# control_logic.net
KiCad netlist of a schematic drawn in Altium Designer
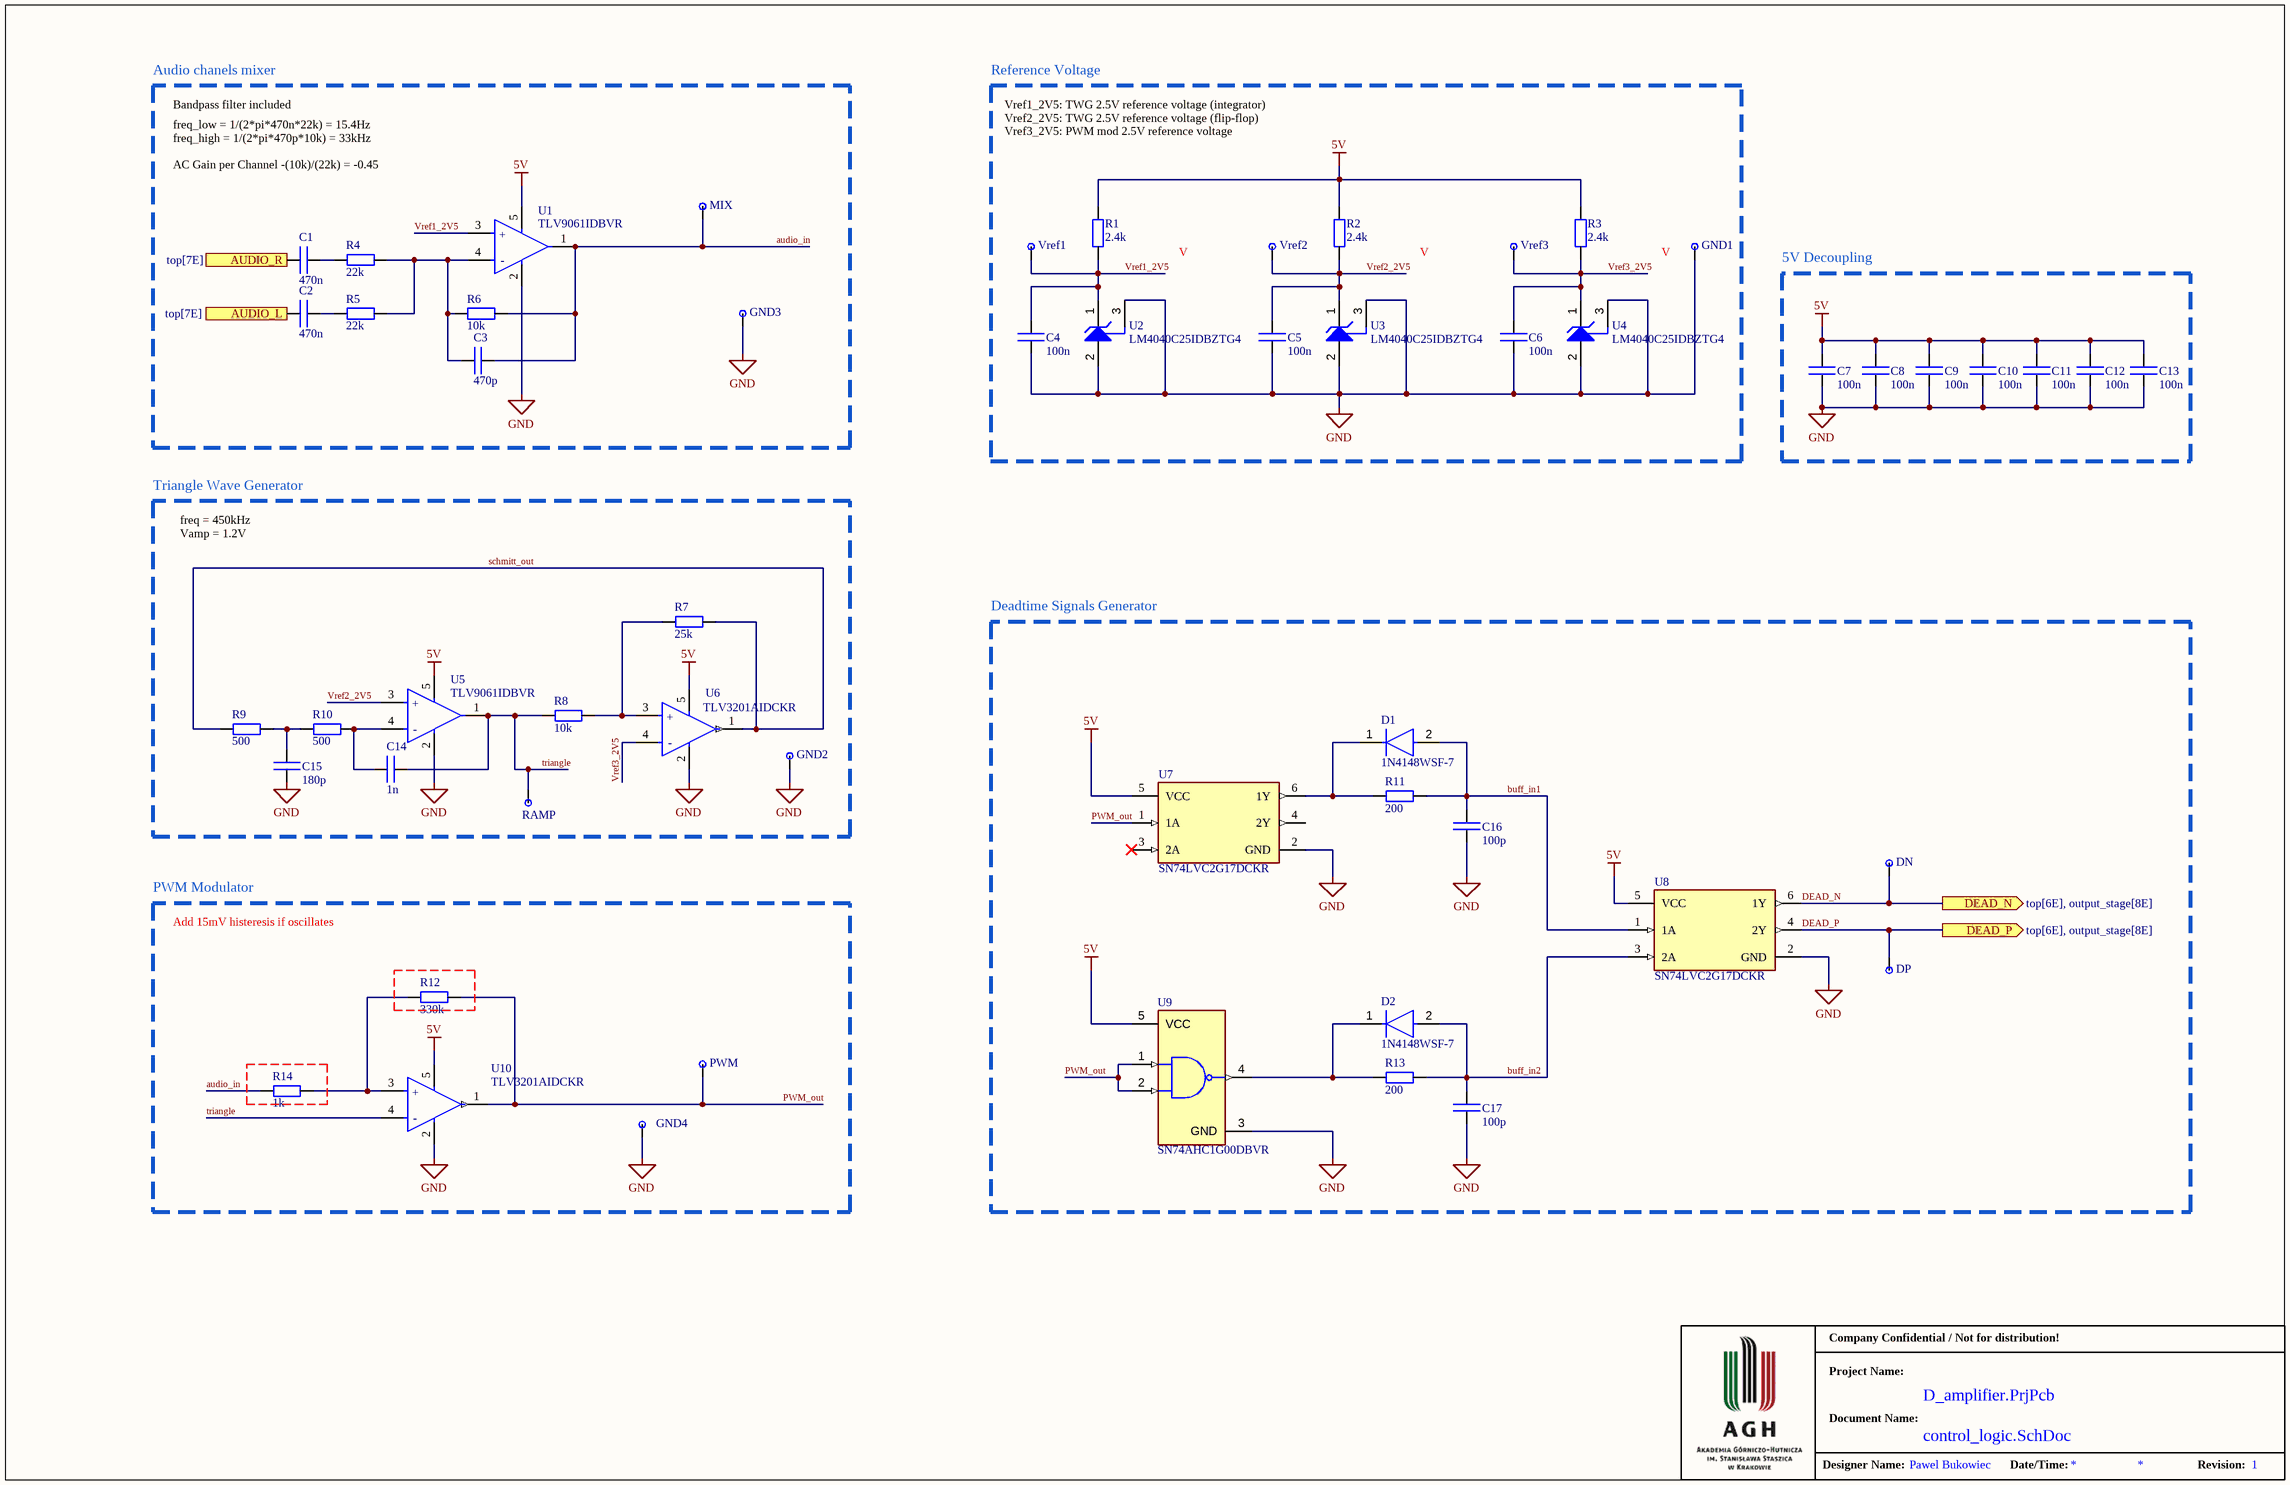
[diagram p0: control_logic.SchDoc]

(export (version "E")
  (design (tool "Eeschema 10.0.6"))
  (components
    (comp (ref "C1") (value "470n") (footprint "CAP_1206") (libsource (lib "INT_lib") (part "Capacitor")))
    (comp (ref "C2") (value "470n") (footprint "CAP_1206") (libsource (lib "INT_lib") (part "Capacitor")))
    (comp (ref "C3")
      (value "470p")
      (footprint "CAP_IPC_0805_133A")
      (fields (field (name "VOLTAGE") "10"))
      (libsource (lib "INT_lib") (part "Capacitor"))
    )
    (comp (ref "C4")
      (value "100n")
      (footprint "CAP_IPC_0805_133A")
      (fields (field (name "VOLTAGE") "16"))
      (libsource (lib "INT_lib") (part "Capacitor"))
    )
    (comp (ref "C5")
      (value "100n")
      (footprint "CAP_IPC_0805_133A")
      (fields (field (name "VOLTAGE") "16"))
      (libsource (lib "INT_lib") (part "Capacitor"))
    )
    (comp (ref "C6")
      (value "100n")
      (footprint "CAP_IPC_0805_133A")
      (fields (field (name "VOLTAGE") "16"))
      (libsource (lib "INT_lib") (part "Capacitor"))
    )
    (comp (ref "C7")
      (value "100n")
      (footprint "CAP_IPC_0805_133A")
      (fields (field (name "VOLTAGE") "16"))
      (libsource (lib "INT_lib") (part "Capacitor"))
    )
    (comp (ref "C8")
      (value "100n")
      (footprint "CAP_IPC_0805_133A")
      (fields (field (name "VOLTAGE") "16"))
      (libsource (lib "INT_lib") (part "Capacitor"))
    )
    (comp (ref "C9")
      (value "100n")
      (footprint "CAP_IPC_0805_133A")
      (fields (field (name "VOLTAGE") "16"))
      (libsource (lib "INT_lib") (part "Capacitor"))
    )
    (comp (ref "C10")
      (value "100n")
      (footprint "CAP_IPC_0805_133A")
      (fields (field (name "VOLTAGE") "16"))
      (libsource (lib "INT_lib") (part "Capacitor"))
    )
    (comp (ref "C11")
      (value "100n")
      (footprint "CAP_IPC_0805_133A")
      (fields (field (name "VOLTAGE") "16"))
      (libsource (lib "INT_lib") (part "Capacitor"))
    )
    (comp (ref "C12")
      (value "100n")
      (footprint "CAP_IPC_0805_133A")
      (fields (field (name "VOLTAGE") "16"))
      (libsource (lib "INT_lib") (part "Capacitor"))
    )
    (comp (ref "C13")
      (value "100n")
      (footprint "CAP_IPC_0805_133A")
      (fields (field (name "VOLTAGE") "16"))
      (libsource (lib "INT_lib") (part "Capacitor"))
    )
    (comp (ref "C14")
      (value "1n")
      (footprint "CAP_IPC_0805_133A")
      (libsource (lib "INT_lib") (part "Capacitor"))
    )
    (comp (ref "C15")
      (value "180p")
      (footprint "CAP_IPC_0805_133A")
      (libsource (lib "INT_lib") (part "Capacitor"))
    )
    (comp (ref "C16")
      (value "100p")
      (footprint "CAP_IPC_0805_133A")
      (libsource (lib "INT_lib") (part "Capacitor"))
    )
    (comp (ref "C17")
      (value "100p")
      (footprint "CAP_IPC_0805_133A")
      (libsource (lib "INT_lib") (part "Capacitor"))
    )
    (comp (ref "D1")
      (value "1N4148WSF-7")
      (footprint "1N4148")
      (description "DIODE GEN PURP 100V 250MA SOD323")
      (fields
        (field (name "MANUFACTURER") "Diodes Inc.")
        (field (name "OCTOPART") "https://octopart.com/1n4148wsf-7-diodes+inc.-33798544")
      )
      (libsource (lib "INT_lib") (part "1N4148"))
    )
    (comp (ref "D2")
      (value "1N4148WSF-7")
      (footprint "1N4148")
      (description "DIODE GEN PURP 100V 250MA SOD323")
      (fields
        (field (name "MANUFACTURER") "Diodes Inc.")
        (field (name "OCTOPART") "https://octopart.com/1n4148wsf-7-diodes+inc.-33798544")
      )
      (libsource (lib "INT_lib") (part "1N4148"))
    )
    (comp (ref "DN")
      (value "TestPoint")
      (footprint "TestPoint_SMT")
      (description "Test Point")
      (libsource (lib "INT_lib") (part "TestPoint"))
    )
    (comp (ref "DP")
      (value "TestPoint")
      (footprint "TestPoint_SMT")
      (description "Test Point")
      (libsource (lib "INT_lib") (part "TestPoint"))
    )
    (comp (ref "GND1")
      (value "TestPoint")
      (footprint "TestPoint_SMT")
      (description "Test Point")
      (libsource (lib "INT_lib") (part "TestPoint"))
    )
    (comp (ref "GND2")
      (value "TestPoint")
      (footprint "TestPoint_SMT")
      (description "Test Point")
      (libsource (lib "INT_lib") (part "TestPoint"))
    )
    (comp (ref "GND3")
      (value "TestPoint")
      (footprint "TestPoint_SMT")
      (description "Test Point")
      (libsource (lib "INT_lib") (part "TestPoint"))
    )
    (comp (ref "GND4")
      (value "TestPoint")
      (footprint "TestPoint_SMT")
      (description "Test Point")
      (libsource (lib "INT_lib") (part "TestPoint"))
    )
    (comp (ref "MIX")
      (value "TestPoint")
      (footprint "TestPoint_SMT")
      (description "Test Point")
      (libsource (lib "INT_lib") (part "TestPoint"))
    )
    (comp (ref "PWM")
      (value "TestPoint")
      (footprint "TestPoint_SMT")
      (description "Test Point")
      (libsource (lib "INT_lib") (part "TestPoint"))
    )
    (comp (ref "R1")
      (value "2.4k")
      (footprint "RES_VJ_0402_MD")
      (libsource (lib "INT_lib") (part "Resistor"))
    )
    (comp (ref "R2")
      (value "2.4k")
      (footprint "RES_VJ_0402_MD")
      (libsource (lib "INT_lib") (part "Resistor"))
    )
    (comp (ref "R3")
      (value "2.4k")
      (footprint "RES_VJ_0402_MD")
      (libsource (lib "INT_lib") (part "Resistor"))
    )
    (comp (ref "R4") (value "22k") (footprint "RES_VJ_0402_MD") (libsource (lib "INT_lib") (part "Resistor")))
    (comp (ref "R5") (value "22k") (footprint "RES_VJ_0402_MD") (libsource (lib "INT_lib") (part "Resistor")))
    (comp (ref "R6") (value "10k") (footprint "RES_VJ_0402_MD") (libsource (lib "INT_lib") (part "Resistor")))
    (comp (ref "R7") (value "25k") (footprint "RES_VJ_0402_MD") (libsource (lib "INT_lib") (part "Resistor")))
    (comp (ref "R8") (value "10k") (footprint "RES_VJ_0402_MD") (libsource (lib "INT_lib") (part "Resistor")))
    (comp (ref "R9") (value "500") (footprint "RES_VJ_0402_MD") (libsource (lib "INT_lib") (part "Resistor")))
    (comp (ref "R10")
      (value "500")
      (footprint "RES_VJ_0402_MD")
      (libsource (lib "INT_lib") (part "Resistor"))
    )
    (comp (ref "R11")
      (value "200")
      (footprint "RES_VJ_0402_MD")
      (libsource (lib "INT_lib") (part "Resistor"))
    )
    (comp (ref "R12")
      (value "330k")
      (footprint "RES_VJ_0402_MD")
      (libsource (lib "INT_lib") (part "Resistor"))
    )
    (comp (ref "R13")
      (value "200")
      (footprint "RES_VJ_0402_MD")
      (libsource (lib "INT_lib") (part "Resistor"))
    )
    (comp (ref "R14") (value "1k") (footprint "RES_VJ_0402_MD") (libsource (lib "INT_lib") (part "Resistor")))
    (comp (ref "RAMP")
      (value "TestPoint")
      (footprint "TestPoint_SMT")
      (description "Test Point")
      (libsource (lib "INT_lib") (part "TestPoint"))
    )
    (comp (ref "U1")
      (value "TLV9061IDBVR")
      (footprint "TLV9061")
      (description "IC CMOS 1 CIRCUIT SOT23-5")
      (libsource (lib "INT_lib") (part "TLV9061"))
    )
    (comp (ref "U2")
      (value "LM4040C25IDBZTG4")
      (footprint "LM4040C25")
      (fields (field (name "MANUFACTURER") "Texas Instruments"))
      (libsource (lib "INT_lib") (part "LM4040C25"))
    )
    (comp (ref "U3")
      (value "LM4040C25IDBZTG4")
      (footprint "LM4040C25")
      (fields (field (name "MANUFACTURER") "Texas Instruments"))
      (libsource (lib "INT_lib") (part "LM4040C25"))
    )
    (comp (ref "U4")
      (value "LM4040C25IDBZTG4")
      (footprint "LM4040C25")
      (fields (field (name "MANUFACTURER") "Texas Instruments"))
      (libsource (lib "INT_lib") (part "LM4040C25"))
    )
    (comp (ref "U5")
      (value "TLV9061IDBVR")
      (footprint "TLV9061")
      (description "IC CMOS 1 CIRCUIT SOT23-5")
      (libsource (lib "INT_lib") (part "TLV9061"))
    )
    (comp (ref "U6")
      (value "TLV3201AIDCKR")
      (footprint "TLV3201")
      (description "IC COMPARATOR RRI SGL SC70-5")
      (libsource (lib "INT_lib") (part "TLV3201"))
    )
    (comp (ref "U7")
      (value "SN74LVC2G17DCKR")
      (footprint "SN74LVC2G17DCKR")
      (description "IC BUF NON-INVERT 5.5V SC70-6")
      (libsource (lib "INT_lib") (part "SN74LVC2G17DCKR"))
    )
    (comp (ref "U8")
      (value "SN74LVC2G17DCKR")
      (footprint "SN74LVC2G17DCKR")
      (description "IC BUF NON-INVERT 5.5V SC70-6")
      (libsource (lib "INT_lib") (part "SN74LVC2G17DCKR"))
    )
    (comp (ref "U9")
      (value "SN74AHC1G00DBVR")
      (footprint "SN74AHC1G00DBVR")
      (description "IC GATE NAND 1CH 2-INP SOT23-5")
      (fields
        (field (name "OCTOPART") "https://octopart.com/sn74ahc1g00dbvr-texas+instruments-464400")
        (field (name "MANUFACTURER") "Texas Instruments")
      )
      (libsource (lib "INT_lib") (part "SN74AHC1G00DBVR"))
    )
    (comp (ref "U10")
      (value "TLV3201AIDCKR")
      (footprint "TLV3201")
      (description "IC COMPARATOR RRI SGL SC70-5")
      (libsource (lib "INT_lib") (part "TLV3201"))
    )
    (comp (ref "Vref1")
      (value "TestPoint")
      (footprint "TestPoint_SMT")
      (description "Test Point")
      (libsource (lib "INT_lib") (part "TestPoint"))
    )
    (comp (ref "Vref2")
      (value "TestPoint")
      (footprint "TestPoint_SMT")
      (description "Test Point")
      (libsource (lib "INT_lib") (part "TestPoint"))
    )
    (comp (ref "Vref3")
      (value "TestPoint")
      (footprint "TestPoint_SMT")
      (description "Test Point")
      (libsource (lib "INT_lib") (part "TestPoint"))
    )
  )
  (nets
    (net (code "1") (name "/AUDIO_L") (class "Default")
      (node (ref "C2") (pin "1") (pinfunction "1_1") (pintype "passive"))
    )
    (net (code "2") (name "/AUDIO_R") (class "Default")
      (node (ref "C1") (pin "1") (pinfunction "1_1") (pintype "passive"))
    )
    (net (code "3") (name "/DEAD_N") (class "Default")
      (node (ref "DN") (pin "1") (pinfunction "1_1") (pintype "passive"))
      (node (ref "U8") (pin "6") (pinfunction "1Y_6") (pintype "output"))
    )
    (net (code "4") (name "/DEAD_P") (class "Default")
      (node (ref "DP") (pin "1") (pinfunction "1_1") (pintype "passive"))
      (node (ref "U8") (pin "4") (pinfunction "2Y_4") (pintype "output"))
    )
    (net (code "5") (name "/PWM_out") (class "Default")
      (node (ref "PWM") (pin "1") (pinfunction "1_1") (pintype "passive"))
      (node (ref "R12") (pin "2") (pinfunction "2_2") (pintype "passive"))
      (node (ref "U10") (pin "1") (pinfunction "OUT_1") (pintype "output"))
      (node (ref "U7") (pin "1") (pinfunction "1A_1") (pintype "input"))
      (node (ref "U9") (pin "1") (pinfunction "A_1") (pintype "input"))
      (node (ref "U9") (pin "2") (pinfunction "B_2") (pintype "input"))
    )
    (net (code "6") (name "/Vref1_2V5") (class "Default")
      (node (ref "C4") (pin "1") (pinfunction "1_1") (pintype "passive"))
      (node (ref "R1") (pin "2") (pinfunction "2_2") (pintype "passive"))
      (node (ref "U1") (pin "3") (pinfunction "IN+_3") (pintype "tri_state"))
      (node (ref "U2") (pin "1") (pinfunction "CATHODE_1") (pintype "passive"))
      (node (ref "Vref1") (pin "1") (pinfunction "1_1") (pintype "passive"))
    )
    (net (code "7") (name "/Vref2_2V5") (class "Default")
      (node (ref "C5") (pin "1") (pinfunction "1_1") (pintype "passive"))
      (node (ref "R2") (pin "2") (pinfunction "2_2") (pintype "passive"))
      (node (ref "U3") (pin "1") (pinfunction "CATHODE_1") (pintype "passive"))
      (node (ref "U5") (pin "3") (pinfunction "IN+_3") (pintype "tri_state"))
      (node (ref "Vref2") (pin "1") (pinfunction "1_1") (pintype "passive"))
    )
    (net (code "8") (name "/Vref3_2V5") (class "Default")
      (node (ref "C6") (pin "1") (pinfunction "1_1") (pintype "passive"))
      (node (ref "R3") (pin "2") (pinfunction "2_2") (pintype "passive"))
      (node (ref "U4") (pin "1") (pinfunction "CATHODE_1") (pintype "passive"))
      (node (ref "U6") (pin "4") (pinfunction "IN-_4") (pintype "tri_state"))
      (node (ref "Vref3") (pin "1") (pinfunction "1_1") (pintype "passive"))
    )
    (net (code "9") (name "/audio_in") (class "Default")
      (node (ref "C3") (pin "2") (pinfunction "2_2") (pintype "passive"))
      (node (ref "MIX") (pin "1") (pinfunction "1_1") (pintype "passive"))
      (node (ref "R14") (pin "1") (pinfunction "1_1") (pintype "passive"))
      (node (ref "R6") (pin "2") (pinfunction "2_2") (pintype "passive"))
      (node (ref "U1") (pin "1") (pinfunction "OUT_1") (pintype "passive"))
    )
    (net (code "10") (name "/buff_in1") (class "Default")
      (node (ref "C16") (pin "1") (pinfunction "1_1") (pintype "passive"))
      (node (ref "D1") (pin "2") (pinfunction "A_2") (pintype "passive"))
      (node (ref "R11") (pin "2") (pinfunction "2_2") (pintype "passive"))
      (node (ref "U8") (pin "1") (pinfunction "1A_1") (pintype "input"))
    )
    (net (code "11") (name "/buff_in2") (class "Default")
      (node (ref "C17") (pin "1") (pinfunction "1_1") (pintype "passive"))
      (node (ref "D2") (pin "2") (pinfunction "A_2") (pintype "passive"))
      (node (ref "R13") (pin "2") (pinfunction "2_2") (pintype "passive"))
      (node (ref "U8") (pin "3") (pinfunction "2A_3") (pintype "input"))
    )
    (net (code "12") (name "/schmitt_out") (class "Default")
      (node (ref "R7") (pin "2") (pinfunction "2_2") (pintype "passive"))
      (node (ref "R9") (pin "1") (pinfunction "1_1") (pintype "passive"))
      (node (ref "U6") (pin "1") (pinfunction "OUT_1") (pintype "output"))
    )
    (net (code "13") (name "/triangle") (class "Default")
      (node (ref "C14") (pin "2") (pinfunction "2_2") (pintype "passive"))
      (node (ref "R8") (pin "1") (pinfunction "1_1") (pintype "passive"))
      (node (ref "RAMP") (pin "1") (pinfunction "1_1") (pintype "passive"))
      (node (ref "U10") (pin "4") (pinfunction "IN-_4") (pintype "tri_state"))
      (node (ref "U5") (pin "1") (pinfunction "OUT_1") (pintype "passive"))
    )
    (net (code "14") (name "5V") (class "Default")
      (node (ref "C10") (pin "1") (pinfunction "1_1") (pintype "passive"))
      (node (ref "C11") (pin "1") (pinfunction "1_1") (pintype "passive"))
      (node (ref "C12") (pin "1") (pinfunction "1_1") (pintype "passive"))
      (node (ref "C13") (pin "1") (pinfunction "1_1") (pintype "passive"))
      (node (ref "C7") (pin "1") (pinfunction "1_1") (pintype "passive"))
      (node (ref "C8") (pin "1") (pinfunction "1_1") (pintype "passive"))
      (node (ref "C9") (pin "1") (pinfunction "1_1") (pintype "passive"))
      (node (ref "R1") (pin "1") (pinfunction "1_1") (pintype "passive"))
      (node (ref "R2") (pin "1") (pinfunction "1_1") (pintype "passive"))
      (node (ref "R3") (pin "1") (pinfunction "1_1") (pintype "passive"))
      (node (ref "U1") (pin "5") (pinfunction "V+_5") (pintype "power_in"))
      (node (ref "U10") (pin "5") (pinfunction "VCC_5") (pintype "power_in"))
      (node (ref "U5") (pin "5") (pinfunction "V+_5") (pintype "power_in"))
      (node (ref "U6") (pin "5") (pinfunction "VCC_5") (pintype "power_in"))
      (node (ref "U7") (pin "5") (pinfunction "VCC_5") (pintype "power_in"))
      (node (ref "U8") (pin "5") (pinfunction "VCC_5") (pintype "power_in"))
      (node (ref "U9") (pin "5") (pinfunction "VCC_5") (pintype "power_in"))
    )
    (net (code "15") (name "GND") (class "Default")
      (node (ref "C10") (pin "2") (pinfunction "2_2") (pintype "passive"))
      (node (ref "C11") (pin "2") (pinfunction "2_2") (pintype "passive"))
      (node (ref "C12") (pin "2") (pinfunction "2_2") (pintype "passive"))
      (node (ref "C13") (pin "2") (pinfunction "2_2") (pintype "passive"))
      (node (ref "C15") (pin "2") (pinfunction "2_2") (pintype "passive"))
      (node (ref "C16") (pin "2") (pinfunction "2_2") (pintype "passive"))
      (node (ref "C17") (pin "2") (pinfunction "2_2") (pintype "passive"))
      (node (ref "C4") (pin "2") (pinfunction "2_2") (pintype "passive"))
      (node (ref "C5") (pin "2") (pinfunction "2_2") (pintype "passive"))
      (node (ref "C6") (pin "2") (pinfunction "2_2") (pintype "passive"))
      (node (ref "C7") (pin "2") (pinfunction "2_2") (pintype "passive"))
      (node (ref "C8") (pin "2") (pinfunction "2_2") (pintype "passive"))
      (node (ref "C9") (pin "2") (pinfunction "2_2") (pintype "passive"))
      (node (ref "GND1") (pin "1") (pinfunction "1_1") (pintype "passive"))
      (node (ref "GND2") (pin "1") (pinfunction "1_1") (pintype "passive"))
      (node (ref "GND3") (pin "1") (pinfunction "1_1") (pintype "passive"))
      (node (ref "GND4") (pin "1") (pinfunction "1_1") (pintype "passive"))
      (node (ref "U1") (pin "2") (pinfunction "V-_2") (pintype "power_in"))
      (node (ref "U10") (pin "2") (pinfunction "GND_2") (pintype "power_in"))
      (node (ref "U2") (pin "2") (pinfunction "ANODE_2") (pintype "passive"))
      (node (ref "U2") (pin "3") (pinfunction "NC_3") (pintype "passive"))
      (node (ref "U3") (pin "2") (pinfunction "ANODE_2") (pintype "passive"))
      (node (ref "U3") (pin "3") (pinfunction "NC_3") (pintype "passive"))
      (node (ref "U4") (pin "2") (pinfunction "ANODE_2") (pintype "passive"))
      (node (ref "U4") (pin "3") (pinfunction "NC_3") (pintype "passive"))
      (node (ref "U5") (pin "2") (pinfunction "V-_2") (pintype "power_in"))
      (node (ref "U6") (pin "2") (pinfunction "GND_2") (pintype "power_in"))
      (node (ref "U7") (pin "2") (pinfunction "GND_2") (pintype "power_in"))
      (node (ref "U8") (pin "2") (pinfunction "GND_2") (pintype "power_in"))
      (node (ref "U9") (pin "3") (pinfunction "GND_3") (pintype "power_in"))
    )
    (net (code "16") (name "Net-(C1-Pad2)") (class "Default")
      (node (ref "C1") (pin "2") (pinfunction "2_2") (pintype "passive"))
      (node (ref "R4") (pin "1") (pinfunction "1_1") (pintype "passive"))
    )
    (net (code "17") (name "Net-(C2-Pad2)") (class "Default")
      (node (ref "C2") (pin "2") (pinfunction "2_2") (pintype "passive"))
      (node (ref "R5") (pin "1") (pinfunction "1_1") (pintype "passive"))
    )
    (net (code "18") (name "Net-(C15-Pad1)") (class "Default")
      (node (ref "C15") (pin "1") (pinfunction "1_1") (pintype "passive"))
      (node (ref "R10") (pin "1") (pinfunction "1_1") (pintype "passive"))
      (node (ref "R9") (pin "2") (pinfunction "2_2") (pintype "passive"))
    )
    (net (code "19") (name "Net-(D1-C)") (class "Default")
      (node (ref "D1") (pin "1") (pinfunction "C_1") (pintype "passive"))
      (node (ref "R11") (pin "1") (pinfunction "1_1") (pintype "passive"))
      (node (ref "U7") (pin "6") (pinfunction "1Y_6") (pintype "output"))
    )
    (net (code "20") (name "Net-(D2-C)") (class "Default")
      (node (ref "D2") (pin "1") (pinfunction "C_1") (pintype "passive"))
      (node (ref "R13") (pin "1") (pinfunction "1_1") (pintype "passive"))
      (node (ref "U9") (pin "4") (pinfunction "Y_4") (pintype "output"))
    )
    (net (code "21") (name "Net-(U1-IN-)") (class "Default")
      (node (ref "C3") (pin "1") (pinfunction "1_1") (pintype "passive"))
      (node (ref "R4") (pin "2") (pinfunction "2_2") (pintype "passive"))
      (node (ref "R5") (pin "2") (pinfunction "2_2") (pintype "passive"))
      (node (ref "R6") (pin "1") (pinfunction "1_1") (pintype "passive"))
      (node (ref "U1") (pin "4") (pinfunction "IN-_4") (pintype "tri_state"))
    )
    (net (code "22") (name "Net-(U5-IN-)") (class "Default")
      (node (ref "C14") (pin "1") (pinfunction "1_1") (pintype "passive"))
      (node (ref "R10") (pin "2") (pinfunction "2_2") (pintype "passive"))
      (node (ref "U5") (pin "4") (pinfunction "IN-_4") (pintype "tri_state"))
    )
    (net (code "23") (name "Net-(U6-IN+)") (class "Default")
      (node (ref "R7") (pin "1") (pinfunction "1_1") (pintype "passive"))
      (node (ref "R8") (pin "2") (pinfunction "2_2") (pintype "passive"))
      (node (ref "U6") (pin "3") (pinfunction "IN+_3") (pintype "tri_state"))
    )
    (net (code "24") (name "Net-(U10-IN+)") (class "Default")
      (node (ref "R12") (pin "1") (pinfunction "1_1") (pintype "passive"))
      (node (ref "R14") (pin "2") (pinfunction "2_2") (pintype "passive"))
      (node (ref "U10") (pin "3") (pinfunction "IN+_3") (pintype "tri_state"))
    )
    (net (code "25") (name "unconnected-(U7-2A-Pad3)") (class "Default")
      (node (ref "U7") (pin "3") (pinfunction "2A_3") (pintype "input+no_connect"))
    )
    (net (code "26") (name "unconnected-(U7-2Y-Pad4)") (class "Default")
      (node (ref "U7") (pin "4") (pinfunction "2Y_4") (pintype "output"))
    )
  )
)
